# FM-Simple-Regen.net
KiCad netlist of a schematic drawn in EAGLE
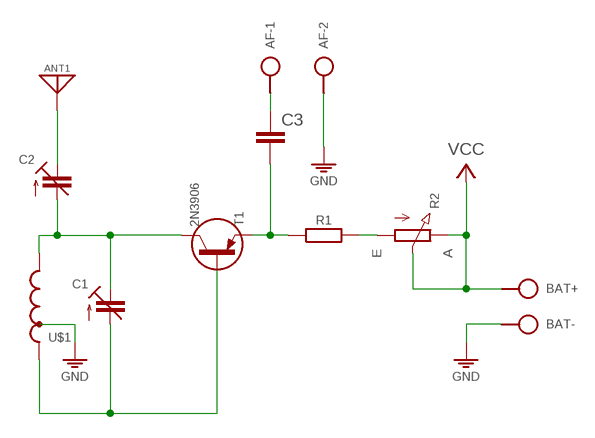
[diagram p0: schematic, sheet 1]

(export (version "E")
  (design (tool "Eeschema 10.0.6"))
  (components
    (comp (ref "AF")
      (value "SPAD-2")
      (footprint "eagle-import:SPAD-2")
      (libsource (lib "eagle-import") (part "SPAD-2"))
    )
    (comp (ref "ANT1")
      (value "ANT")
      (footprint "eagle-import:SPAD")
      (libsource (lib "eagle-import") (part "ANT"))
    )
    (comp (ref "BAT+")
      (value "SPAD")
      (footprint "eagle-import:SPAD")
      (libsource (lib "eagle-import") (part "SPAD"))
    )
    (comp (ref "BAT-")
      (value "SPAD")
      (footprint "eagle-import:SPAD")
      (libsource (lib "eagle-import") (part "SPAD"))
    )
    (comp (ref "C1")
      (value "C-TR-PH201272222-808-2PINB")
      (footprint "eagle-import:TRIM-2222-808")
      (libsource (lib "eagle-import") (part "C-TR-PH201272222-808-2PINB"))
    )
    (comp (ref "C2")
      (value "C-TR-PH201272222-808-2PIN")
      (footprint "eagle-import:TRIM-2222-808")
      (libsource (lib "eagle-import") (part "C-TR-PH201272222-808-2PIN"))
    )
    (comp (ref "C3")
      (value "C050-024X044")
      (footprint "eagle-import:C050-024X044")
      (libsource (lib "eagle-import") (part "C050-024X044"))
    )
    (comp (ref "R1")
      (value "R-H0204/10")
      (footprint "eagle-import:0204_10")
      (libsource (lib "eagle-import") (part "R-H0204/10"))
    )
    (comp (ref "R2")
      (value "POT")
      (footprint "eagle-import:POT")
      (libsource (lib "eagle-import") (part "POT"))
    )
    (comp (ref "T1")
      (value "2N3906")
      (footprint "eagle-import:TO92")
      (libsource (lib "eagle-import") (part "2N3906"))
    )
    (comp (ref "U$1")
      (value "L-TAP104/7")
      (footprint "eagle-import:L-04_10-TAP1")
      (libsource (lib "eagle-import") (part "L-TAP104/7"))
    )
  )
  (nets
    (net (code "1") (name "GND") (class "Default")
      (node (ref "AF") (pin "2") (pinfunction "P$1_2") (pintype "passive"))
      (node (ref "BAT-") (pin "1") (pinfunction "P$1_1") (pintype "passive"))
      (node (ref "U$1") (pin "T") (pinfunction "T_T") (pintype "passive"))
    )
    (net (code "2") (name "Net-(AFA-P$1)") (class "Default")
      (node (ref "AF") (pin "1") (pinfunction "P$1_1") (pintype "passive"))
      (node (ref "C3") (pin "1") (pinfunction "1_1") (pintype "passive"))
    )
    (net (code "3") (name "Net-(C1-A)") (class "Default")
      (node (ref "C1") (pin "2") (pinfunction "A_2") (pintype "passive"))
      (node (ref "T1") (pin "2") (pinfunction "B_2") (pintype "passive"))
      (node (ref "U$1") (pin "1") (pinfunction "1_1") (pintype "passive"))
    )
    (net (code "4") (name "Net-(C1-E)") (class "Default")
      (node (ref "C1") (pin "3") (pinfunction "E_3") (pintype "passive"))
      (node (ref "C2") (pin "2") (pinfunction "A_2") (pintype "passive"))
      (node (ref "T1") (pin "3") (pinfunction "C_3") (pintype "passive"))
      (node (ref "U$1") (pin "2") (pinfunction "2_2") (pintype "passive"))
    )
    (net (code "5") (name "Net-(C2-E)") (class "Default")
      (node (ref "ANT1") (pin "1") (pinfunction "1_1") (pintype "output"))
      (node (ref "C2") (pin "1") (pinfunction "E_1") (pintype "passive"))
    )
    (net (code "6") (name "Net-(R1-Pad2)") (class "Default")
      (node (ref "R1") (pin "2") (pinfunction "2_2") (pintype "passive"))
      (node (ref "R2") (pin "A") (pinfunction "A_A") (pintype "passive"))
    )
    (net (code "7") (name "Net-(T1-E)") (class "Default")
      (node (ref "C3") (pin "2") (pinfunction "2_2") (pintype "passive"))
      (node (ref "R1") (pin "1") (pinfunction "1_1") (pintype "passive"))
      (node (ref "T1") (pin "1") (pinfunction "E_1") (pintype "passive"))
    )
    (net (code "8") (name "VCC") (class "Default")
      (node (ref "BAT+") (pin "1") (pinfunction "P$1_1") (pintype "passive"))
      (node (ref "R2") (pin "E") (pinfunction "E_E") (pintype "passive"))
      (node (ref "R2") (pin "S") (pinfunction "S_S") (pintype "passive"))
    )
  )
)
